# v1_0.net
KiCad netlist of a schematic drawn in Altium Designer
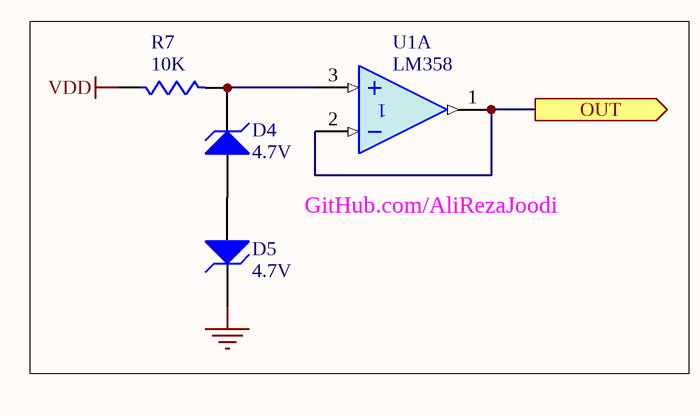
[diagram p0: v1.0.SchDoc]

(export (version "E")
  (design (tool "Eeschema 10.0.6"))
  (components
    (comp (ref "D4")
      (value "4.7V")
      (footprint "DIODE0.4_Glass")
      (description "Zener Diode")
      (fields (field (name "MANUFACTURER") "Generic Components") (field (name "PUBLISHER") "Altium Limited"))
      (libsource (lib "Miscellaneous Devices") (part "D Zener"))
    )
    (comp (ref "D5")
      (value "4.7V")
      (footprint "DIODE0.4_Glass")
      (description "Zener Diode")
      (fields (field (name "MANUFACTURER") "Generic Components") (field (name "PUBLISHER") "Altium Limited"))
      (libsource (lib "Miscellaneous Devices") (part "D Zener"))
    )
    (comp (ref "R7")
      (value "10K")
      (footprint "AXIAL-0.4")
      (description "Resistor")
      (fields (field (name "MANUFACTURER") "Generic Components") (field (name "PUBLISHER") "Altium Limited"))
      (libsource (lib "Miscellaneous Devices") (part "Res1"))
    )
    (comp (ref "U1")
      (value "LM358")
      (footprint "DIP_8")
      (description "Dual Low-Power Operational Amplifier")
      (fields (field (name "PUBLISHER") "Altium Limited"))
      (libsource (lib "Op-Amp") (part "LM358"))
    )
  )
  (nets
    (net (code "1") (name "/OUT") (class "Default")
      (node (ref "U1") (pin "1") (pinfunction "OUT_1") (pintype "output"))
      (node (ref "U1") (pin "2") (pinfunction "IN-_2") (pintype "input"))
    )
    (net (code "2") (name "GND") (class "Default")
      (node (ref "D5") (pin "2") (pinfunction "K_2") (pintype "passive"))
    )
    (net (code "3") (name "Net-(D4-A)") (class "Default")
      (node (ref "D4") (pin "1") (pinfunction "A_1") (pintype "passive"))
      (node (ref "D5") (pin "1") (pinfunction "A_1") (pintype "passive"))
    )
    (net (code "4") (name "Net-(D4-K)") (class "Default")
      (node (ref "D4") (pin "2") (pinfunction "K_2") (pintype "passive"))
      (node (ref "R7") (pin "2") (pinfunction "2_2") (pintype "passive"))
      (node (ref "U1") (pin "3") (pinfunction "IN+_3") (pintype "input"))
    )
    (net (code "5") (name "VDD") (class "Default")
      (node (ref "R7") (pin "1") (pinfunction "1_1") (pintype "passive"))
    )
  )
)
